# LAB-PLR1010.net
KiCad netlist of a schematic drawn in EAGLE
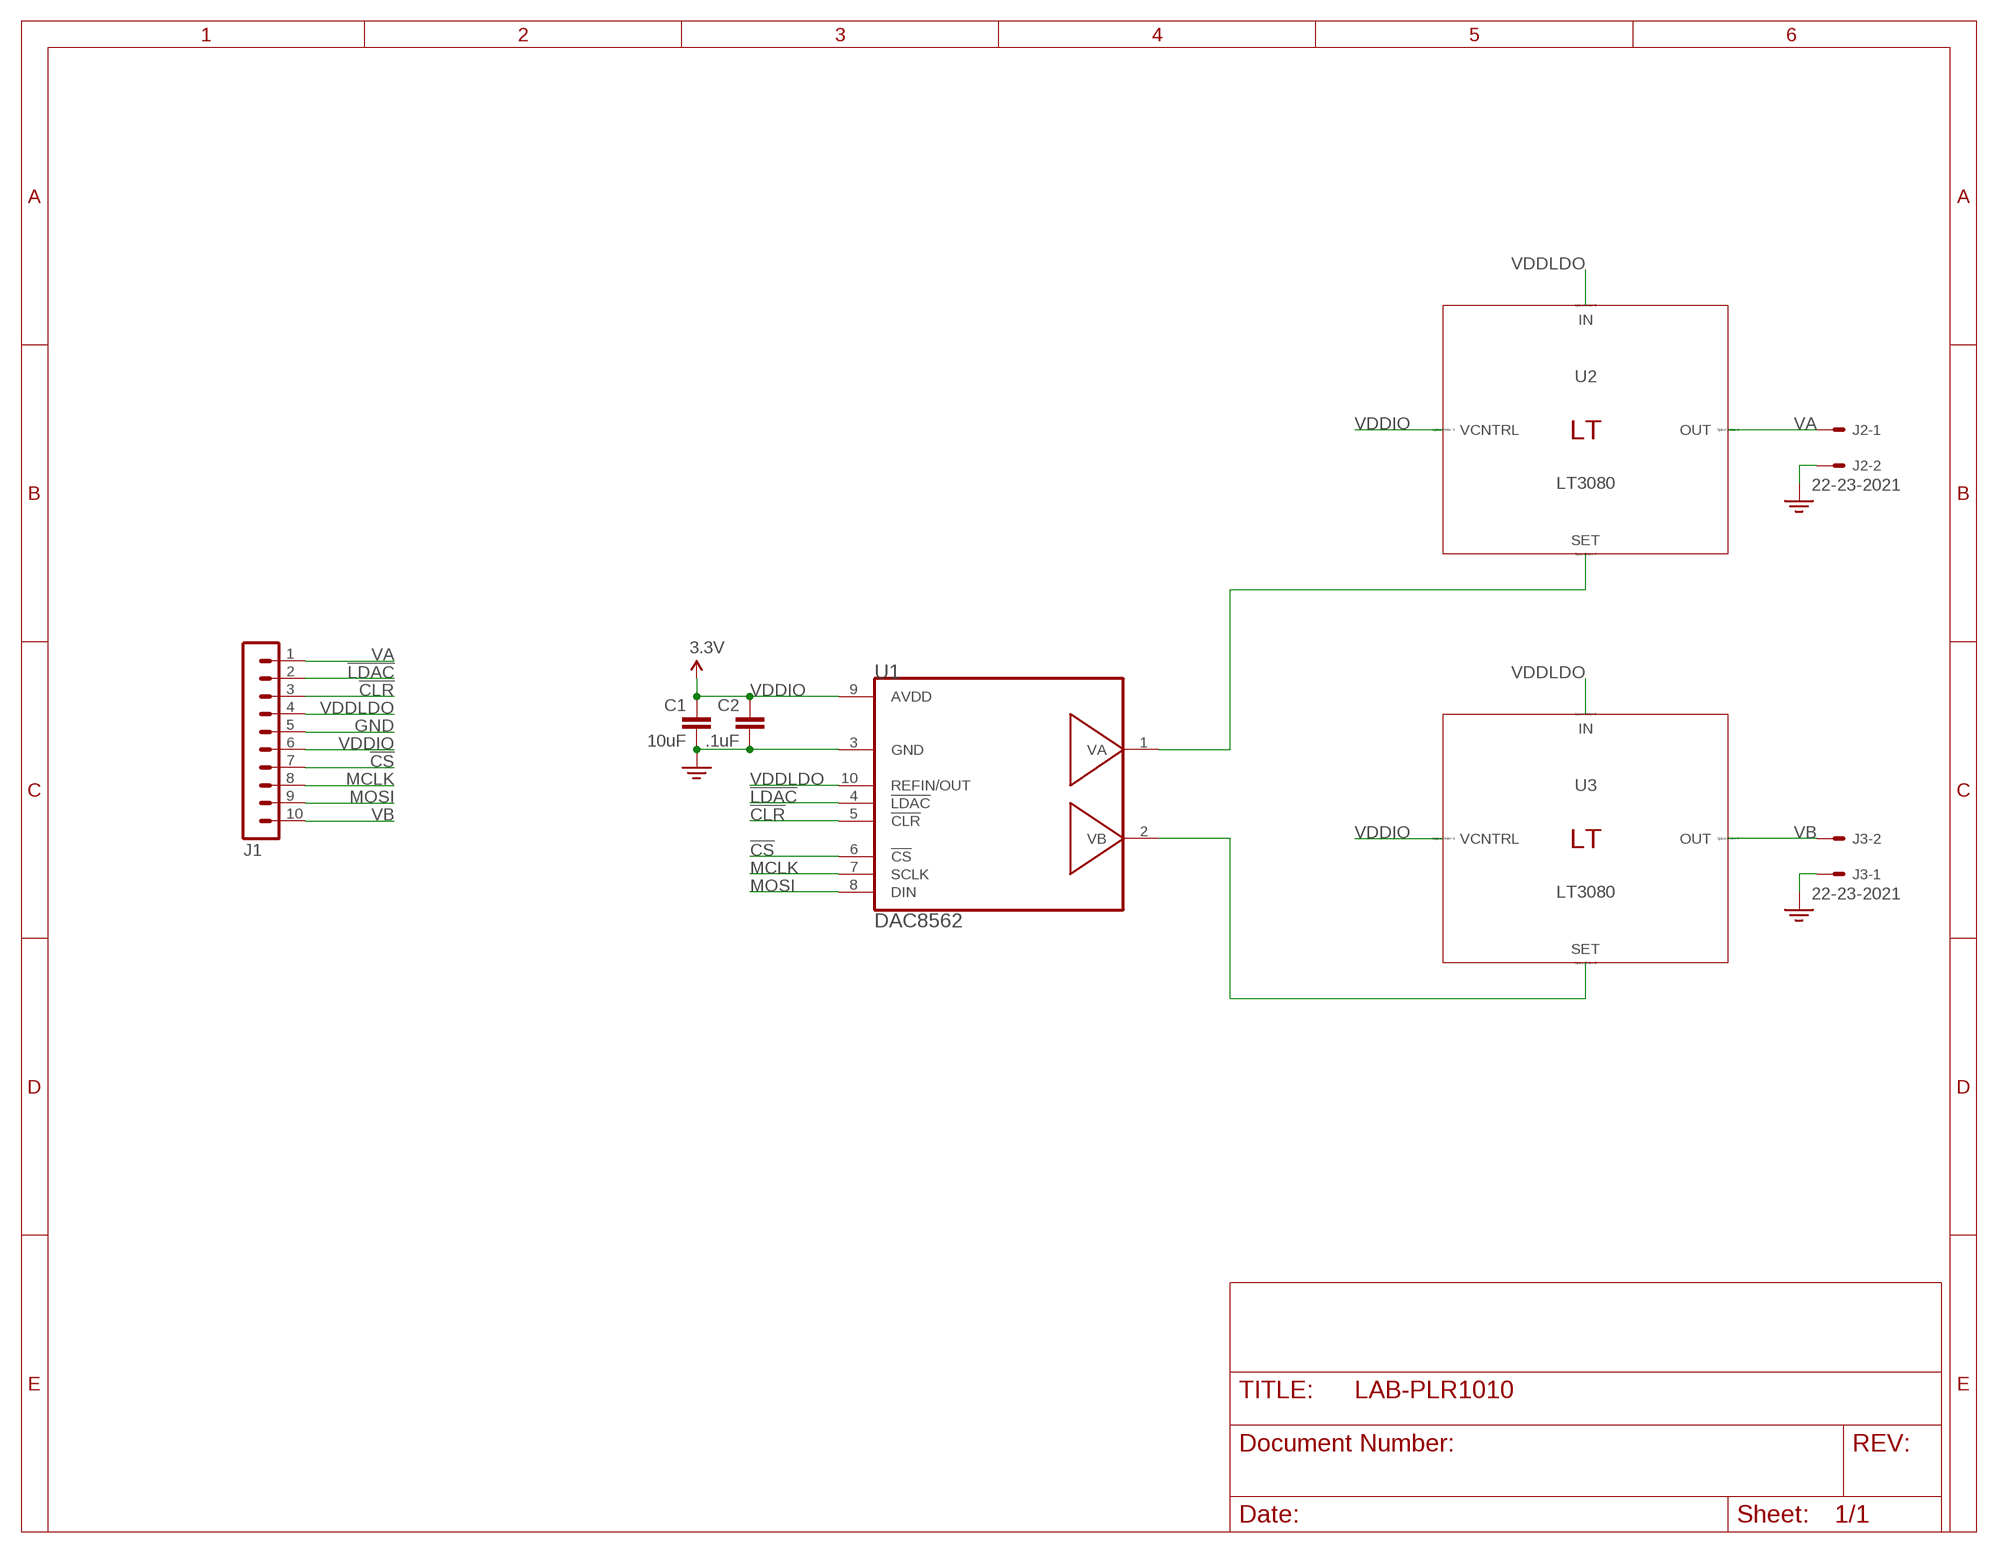
[diagram p0: schematic, sheet 1]

(export (version "E")
  (design (tool "Eeschema 10.0.6"))
  (components
    (comp (ref "C1")
      (value "10uF")
      (footprint "eagle-import:0603-CAP")
      (libsource (lib "eagle-import") (part "1NF/1000PF-50V-10%(0603)"))
    )
    (comp (ref "C2")
      (value ".1uF")
      (footprint "eagle-import:0603-CAP")
      (libsource (lib "eagle-import") (part "1NF/1000PF-50V-10%(0603)"))
    )
    (comp (ref "J1")
      (value "MA10-1W")
      (footprint "eagle-import:MA10-1W")
      (libsource (lib "eagle-import") (part "MA10-1W"))
    )
    (comp (ref "J2")
      (value "22-23-2021")
      (footprint "eagle-import:22-23-2021")
      (libsource (lib "eagle-import") (part "22-23-2021"))
    )
    (comp (ref "J3")
      (value "22-23-2021")
      (footprint "eagle-import:22-23-2021")
      (libsource (lib "eagle-import") (part "22-23-2021"))
    )
    (comp (ref "U1")
      (value "DAC8562")
      (footprint "eagle-import:MSOP10")
      (libsource (lib "eagle-import") (part "DAC8562"))
    )
    (comp (ref "U2")
      (value "LT3080")
      (footprint "eagle-import:DDPAK5(Q)")
      (libsource (lib "eagle-import") (part "LT3080"))
    )
    (comp (ref "U3")
      (value "LT3080")
      (footprint "eagle-import:DDPAK5(Q)")
      (libsource (lib "eagle-import") (part "LT3080"))
    )
  )
  (nets
    (net (code "1") (name "/MCLK") (class "Default")
      (node (ref "J1") (pin "8") (pinfunction "8_8") (pintype "passive"))
      (node (ref "U1") (pin "7") (pinfunction "SCLK_7") (pintype "input"))
    )
    (net (code "2") (name "/MOSI") (class "Default")
      (node (ref "J1") (pin "9") (pinfunction "9_9") (pintype "passive"))
      (node (ref "U1") (pin "8") (pinfunction "DIN_8") (pintype "input"))
    )
    (net (code "3") (name "/VA") (class "Default")
      (node (ref "J1") (pin "1") (pinfunction "1_1") (pintype "passive"))
      (node (ref "J2") (pin "1") (pinfunction "S_1") (pintype "passive"))
      (node (ref "U2") (pin "3") (pinfunction "OUT_3") (pintype "passive"))
      (node (ref "U2") (pin "TAB") (pinfunction "OUT_TAB") (pintype "passive"))
    )
    (net (code "4") (name "/VB") (class "Default")
      (node (ref "J1") (pin "10") (pinfunction "10_10") (pintype "passive"))
      (node (ref "J3") (pin "2") (pinfunction "S_2") (pintype "passive"))
      (node (ref "U3") (pin "3") (pinfunction "OUT_3") (pintype "passive"))
      (node (ref "U3") (pin "TAB") (pinfunction "OUT_TAB") (pintype "passive"))
    )
    (net (code "5") (name "/VDDLDO") (class "Default")
      (node (ref "J1") (pin "4") (pinfunction "4_4") (pintype "passive"))
      (node (ref "U1") (pin "10") (pinfunction "REFIN/OUT_10") (pintype "bidirectional"))
      (node (ref "U2") (pin "5") (pinfunction "IN_5") (pintype "passive"))
      (node (ref "U3") (pin "5") (pinfunction "IN_5") (pintype "passive"))
    )
    (net (code "6") (name "/~{CLR}") (class "Default")
      (node (ref "J1") (pin "3") (pinfunction "3_3") (pintype "passive"))
      (node (ref "U1") (pin "5") (pinfunction "~{CLR}_5") (pintype "output"))
    )
    (net (code "7") (name "/~{CS}") (class "Default")
      (node (ref "J1") (pin "7") (pinfunction "7_7") (pintype "passive"))
      (node (ref "U1") (pin "6") (pinfunction "~{CS}_6") (pintype "input"))
    )
    (net (code "8") (name "/~{LDAC}") (class "Default")
      (node (ref "J1") (pin "2") (pinfunction "2_2") (pintype "passive"))
      (node (ref "U1") (pin "4") (pinfunction "~{LDAC}_4") (pintype "output"))
    )
    (net (code "9") (name "3.3V") (class "Default")
      (node (ref "C1") (pin "1") (pinfunction "1_1") (pintype "passive"))
      (node (ref "C2") (pin "1") (pinfunction "1_1") (pintype "passive"))
      (node (ref "J1") (pin "6") (pinfunction "6_6") (pintype "passive"))
      (node (ref "U1") (pin "9") (pinfunction "AVDD_9") (pintype "power_in"))
      (node (ref "U2") (pin "4") (pinfunction "VCNTRL_4") (pintype "passive"))
      (node (ref "U3") (pin "4") (pinfunction "VCNTRL_4") (pintype "passive"))
    )
    (net (code "10") (name "Net-(U1-VA)") (class "Default")
      (node (ref "U1") (pin "1") (pinfunction "VA_1") (pintype "output"))
      (node (ref "U2") (pin "2") (pinfunction "SET_2") (pintype "passive"))
    )
    (net (code "11") (name "Net-(U1-VB)") (class "Default")
      (node (ref "U1") (pin "2") (pinfunction "VB_2") (pintype "output"))
      (node (ref "U3") (pin "2") (pinfunction "SET_2") (pintype "passive"))
    )
    (net (code "12") (name "gnd") (class "Default")
      (node (ref "C1") (pin "2") (pinfunction "2_2") (pintype "passive"))
      (node (ref "C2") (pin "2") (pinfunction "2_2") (pintype "passive"))
      (node (ref "J1") (pin "5") (pinfunction "5_5") (pintype "passive"))
      (node (ref "J2") (pin "2") (pinfunction "S_2") (pintype "passive"))
      (node (ref "J3") (pin "1") (pinfunction "S_1") (pintype "passive"))
      (node (ref "U1") (pin "3") (pinfunction "GND_3") (pintype "power_in"))
    )
  )
)
